# TowerLight.net
KiCad netlist of a schematic drawn in EAGLE
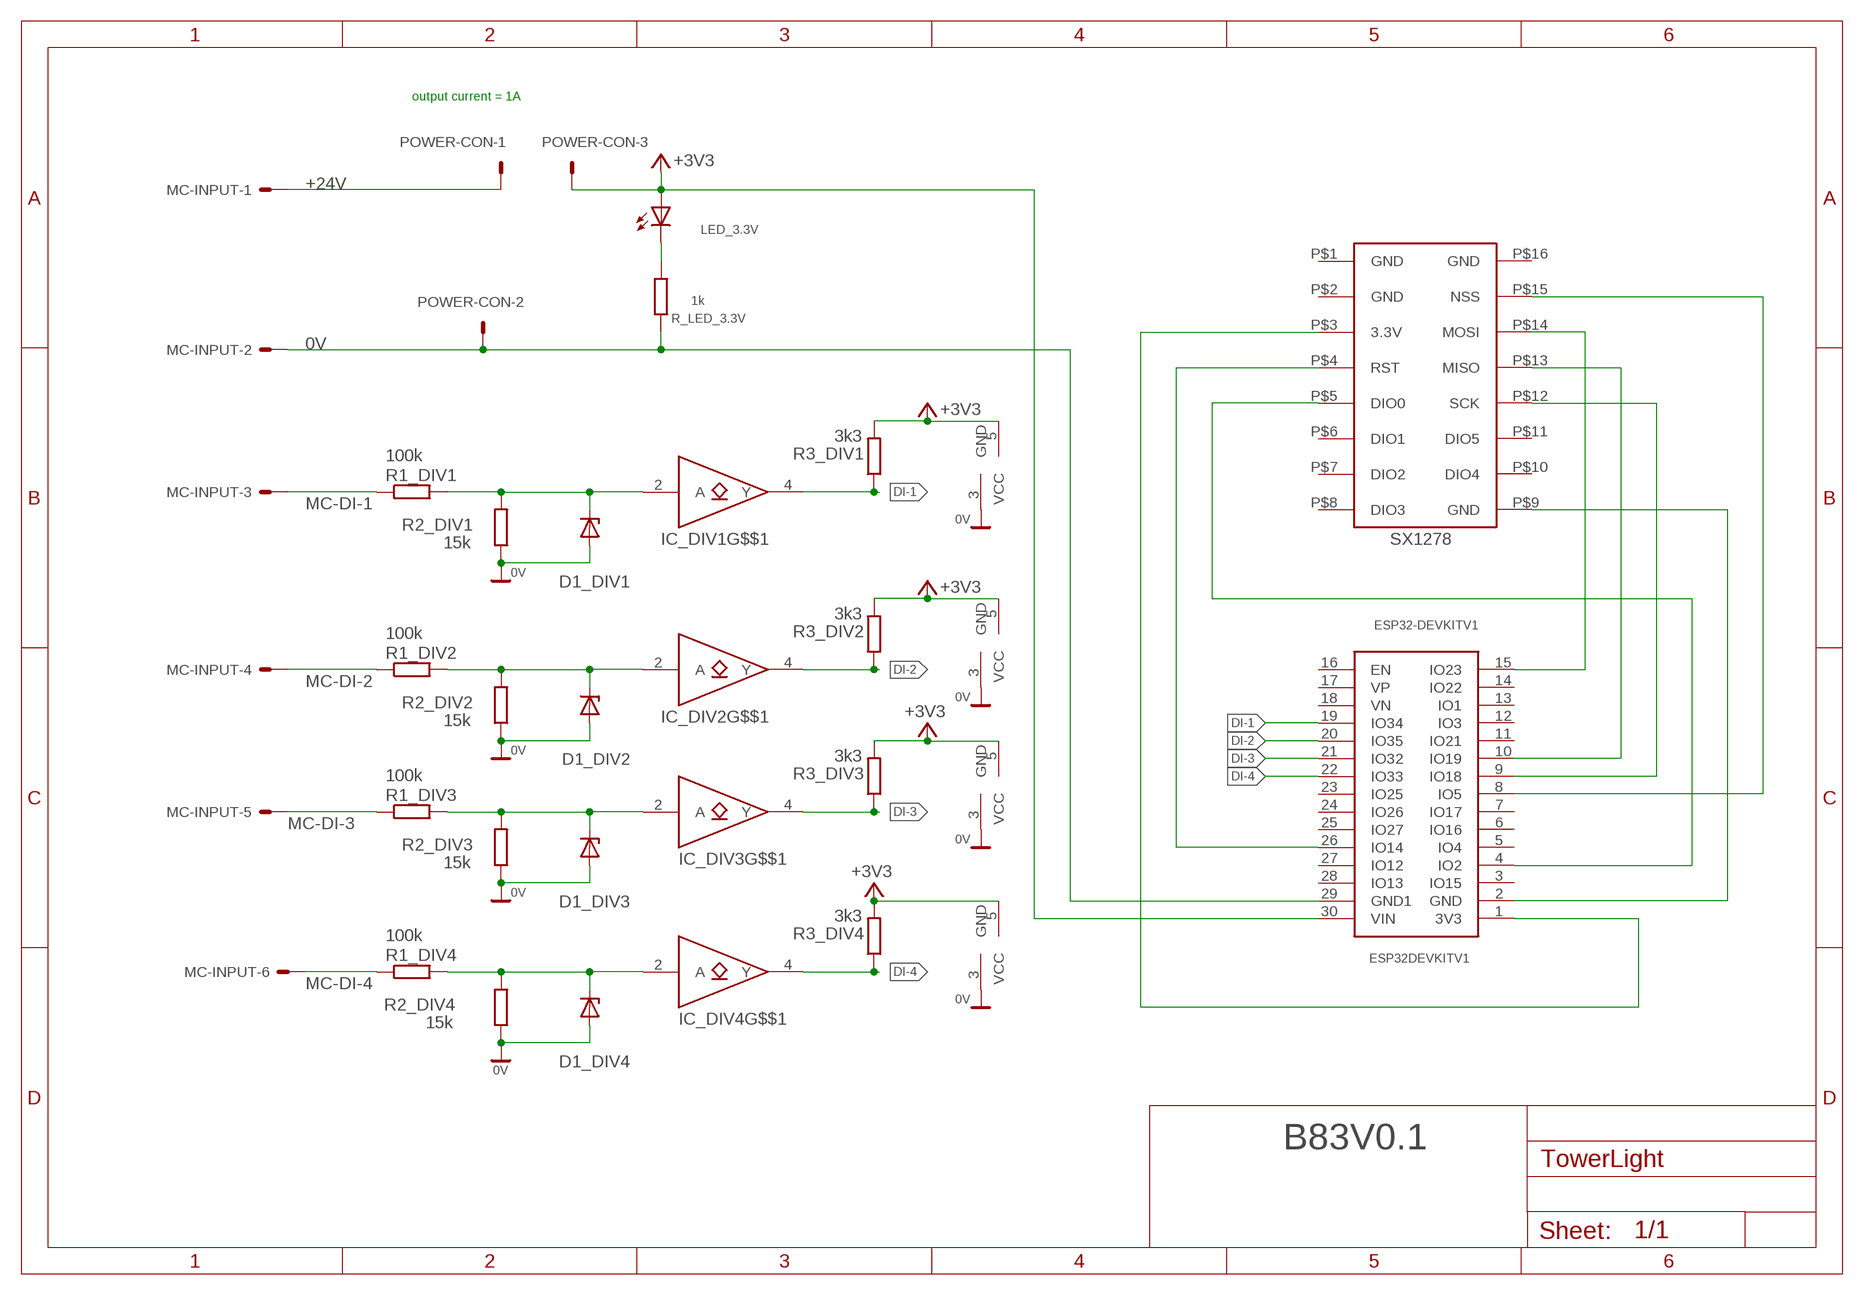
[diagram p0: schematic, sheet 1]

(export (version "E")
  (design (tool "Eeschema 10.0.6"))
  (components
    (comp (ref "D1_DIV1")
      (value "ZENER-DIODEDO34-7")
      (footprint "eagle-import:DO34Z7")
      (libsource (lib "eagle-import") (part "ZENER-DIODEDO34-7"))
    )
    (comp (ref "D1_DIV2")
      (value "ZENER-DIODEDO34-7")
      (footprint "eagle-import:DO34Z7")
      (libsource (lib "eagle-import") (part "ZENER-DIODEDO34-7"))
    )
    (comp (ref "D1_DIV3")
      (value "ZENER-DIODEDO34-7")
      (footprint "eagle-import:DO34Z7")
      (libsource (lib "eagle-import") (part "ZENER-DIODEDO34-7"))
    )
    (comp (ref "D1_DIV4")
      (value "ZENER-DIODEDO34-7")
      (footprint "eagle-import:DO34Z7")
      (libsource (lib "eagle-import") (part "ZENER-DIODEDO34-7"))
    )
    (comp (ref "ESP32DEVKITV1")
      (value "ESP32DEVKITV1")
      (footprint "eagle-import:ESP32-DEVKITV1")
      (libsource (lib "eagle-import") (part "ESP32DEVKITV1"))
    )
    (comp (ref "IC_DIV1")
      (value "SN74LVC1G07DBVR")
      (footprint "eagle-import:SOT23-5L")
      (libsource (lib "eagle-import") (part "SN74LVC1G07DBVR"))
    )
    (comp (ref "IC_DIV2")
      (value "SN74LVC1G07DBVR")
      (footprint "eagle-import:SOT23-5L")
      (libsource (lib "eagle-import") (part "SN74LVC1G07DBVR"))
    )
    (comp (ref "IC_DIV3")
      (value "SN74LVC1G07DBVR")
      (footprint "eagle-import:SOT23-5L")
      (libsource (lib "eagle-import") (part "SN74LVC1G07DBVR"))
    )
    (comp (ref "IC_DIV4")
      (value "SN74LVC1G07DBVR")
      (footprint "eagle-import:SOT23-5L")
      (libsource (lib "eagle-import") (part "SN74LVC1G07DBVR"))
    )
    (comp (ref "LED_3.3V")
      (value "LED_SUB")
      (footprint "eagle-import:LED_SUBMINI")
      (libsource (lib "eagle-import") (part "LED_SUB"))
    )
    (comp (ref "MC-INPUT")
      (value "22-05-7068-06")
      (footprint "eagle-import:7395-06")
      (libsource (lib "eagle-import") (part "22-?-0605-7068"))
    )
    (comp (ref "POWER-CON")
      (value "22-05-7038-03")
      (footprint "eagle-import:7395-03")
      (libsource (lib "eagle-import") (part "22-?-0305-7038"))
    )
    (comp (ref "R1_DIV1")
      (value "100k")
      (footprint "eagle-import:R1206")
      (libsource (lib "eagle-import") (part "R-EU_R1206"))
    )
    (comp (ref "R1_DIV2")
      (value "100k")
      (footprint "eagle-import:R1206")
      (libsource (lib "eagle-import") (part "R-EU_R1206"))
    )
    (comp (ref "R1_DIV3")
      (value "100k")
      (footprint "eagle-import:R1206")
      (libsource (lib "eagle-import") (part "R-EU_R1206"))
    )
    (comp (ref "R1_DIV4")
      (value "100k")
      (footprint "eagle-import:R1206")
      (libsource (lib "eagle-import") (part "R-EU_R1206"))
    )
    (comp (ref "R2_DIV1")
      (value "15k")
      (footprint "eagle-import:R1206")
      (libsource (lib "eagle-import") (part "R-EU_R1206"))
    )
    (comp (ref "R2_DIV2")
      (value "15k")
      (footprint "eagle-import:R1206")
      (libsource (lib "eagle-import") (part "R-EU_R1206"))
    )
    (comp (ref "R2_DIV3")
      (value "15k")
      (footprint "eagle-import:R1206")
      (libsource (lib "eagle-import") (part "R-EU_R1206"))
    )
    (comp (ref "R2_DIV4")
      (value "15k")
      (footprint "eagle-import:R1206")
      (libsource (lib "eagle-import") (part "R-EU_R1206"))
    )
    (comp (ref "R3_DIV1")
      (value "3k3")
      (footprint "eagle-import:R1206")
      (libsource (lib "eagle-import") (part "R-EU_R1206"))
    )
    (comp (ref "R3_DIV2")
      (value "3k3")
      (footprint "eagle-import:R1206")
      (libsource (lib "eagle-import") (part "R-EU_R1206"))
    )
    (comp (ref "R3_DIV3")
      (value "3k3")
      (footprint "eagle-import:R1206")
      (libsource (lib "eagle-import") (part "R-EU_R1206"))
    )
    (comp (ref "R3_DIV4")
      (value "3k3")
      (footprint "eagle-import:R1206")
      (libsource (lib "eagle-import") (part "R-EU_R1206"))
    )
    (comp (ref "R_LED_3.3V")
      (value "1k")
      (footprint "eagle-import:R1206")
      (libsource (lib "eagle-import") (part "R-EU_R1206"))
    )
    (comp (ref "U$2")
      (value "SX1278_MODULE")
      (footprint "eagle-import:SX1278_MODULE")
      (libsource (lib "eagle-import") (part "SX1278_MODULE"))
    )
  )
  (nets
    (net (code "1") (name "+3V3") (class "Default")
      (node (ref "ESP32DEVKITV1") (pin "30") (pinfunction "VIN_30") (pintype "bidirectional"))
      (node (ref "IC_DIV1") (pin "5") (pinfunction "VCC_5") (pintype "power_in"))
      (node (ref "IC_DIV2") (pin "5") (pinfunction "VCC_5") (pintype "power_in"))
      (node (ref "IC_DIV3") (pin "5") (pinfunction "VCC_5") (pintype "power_in"))
      (node (ref "IC_DIV4") (pin "5") (pinfunction "VCC_5") (pintype "power_in"))
      (node (ref "LED_3.3V") (pin "P$1") (pinfunction "A_P$1") (pintype "passive"))
      (node (ref "POWER-CON") (pin "3") (pinfunction "S_3") (pintype "passive"))
      (node (ref "R3_DIV1") (pin "2") (pinfunction "2_2") (pintype "passive"))
      (node (ref "R3_DIV2") (pin "2") (pinfunction "2_2") (pintype "passive"))
      (node (ref "R3_DIV3") (pin "2") (pinfunction "2_2") (pintype "passive"))
      (node (ref "R3_DIV4") (pin "2") (pinfunction "2_2") (pintype "passive"))
    )
    (net (code "2") (name "/+24V") (class "Default")
      (node (ref "MC-INPUT") (pin "1") (pinfunction "S_1") (pintype "passive"))
      (node (ref "POWER-CON") (pin "1") (pinfunction "S_1") (pintype "passive"))
    )
    (net (code "3") (name "/MC-DI-1") (class "Default")
      (node (ref "MC-INPUT") (pin "3") (pinfunction "S_3") (pintype "passive"))
      (node (ref "R1_DIV1") (pin "1") (pinfunction "1_1") (pintype "passive"))
    )
    (net (code "4") (name "/MC-DI-2") (class "Default")
      (node (ref "MC-INPUT") (pin "4") (pinfunction "S_4") (pintype "passive"))
      (node (ref "R1_DIV2") (pin "1") (pinfunction "1_1") (pintype "passive"))
    )
    (net (code "5") (name "/MC-DI-3") (class "Default")
      (node (ref "MC-INPUT") (pin "5") (pinfunction "S_5") (pintype "passive"))
      (node (ref "R1_DIV3") (pin "1") (pinfunction "1_1") (pintype "passive"))
    )
    (net (code "6") (name "/MC-DI-4") (class "Default")
      (node (ref "MC-INPUT") (pin "6") (pinfunction "S_6") (pintype "passive"))
      (node (ref "R1_DIV4") (pin "1") (pinfunction "1_1") (pintype "passive"))
    )
    (net (code "7") (name "0V") (class "Default")
      (node (ref "D1_DIV1") (pin "A") (pinfunction "A_A") (pintype "passive"))
      (node (ref "D1_DIV2") (pin "A") (pinfunction "A_A") (pintype "passive"))
      (node (ref "D1_DIV3") (pin "A") (pinfunction "A_A") (pintype "passive"))
      (node (ref "D1_DIV4") (pin "A") (pinfunction "A_A") (pintype "passive"))
      (node (ref "ESP32DEVKITV1") (pin "29") (pinfunction "GND1_29") (pintype "bidirectional"))
      (node (ref "IC_DIV1") (pin "3") (pinfunction "GND_3") (pintype "power_in"))
      (node (ref "IC_DIV2") (pin "3") (pinfunction "GND_3") (pintype "power_in"))
      (node (ref "IC_DIV3") (pin "3") (pinfunction "GND_3") (pintype "power_in"))
      (node (ref "IC_DIV4") (pin "3") (pinfunction "GND_3") (pintype "power_in"))
      (node (ref "MC-INPUT") (pin "2") (pinfunction "S_2") (pintype "passive"))
      (node (ref "POWER-CON") (pin "2") (pinfunction "S_2") (pintype "passive"))
      (node (ref "R2_DIV1") (pin "1") (pinfunction "1_1") (pintype "passive"))
      (node (ref "R2_DIV2") (pin "1") (pinfunction "1_1") (pintype "passive"))
      (node (ref "R2_DIV3") (pin "1") (pinfunction "1_1") (pintype "passive"))
      (node (ref "R2_DIV4") (pin "1") (pinfunction "1_1") (pintype "passive"))
      (node (ref "R_LED_3.3V") (pin "2") (pinfunction "2_2") (pintype "passive"))
    )
    (net (code "8") (name "DI-1") (class "Default")
      (node (ref "ESP32DEVKITV1") (pin "19") (pinfunction "IO34_19") (pintype "bidirectional"))
      (node (ref "IC_DIV1") (pin "4") (pinfunction "Y_4") (pintype "bidirectional"))
      (node (ref "R3_DIV1") (pin "1") (pinfunction "1_1") (pintype "passive"))
    )
    (net (code "9") (name "DI-2") (class "Default")
      (node (ref "ESP32DEVKITV1") (pin "20") (pinfunction "IO35_20") (pintype "bidirectional"))
      (node (ref "IC_DIV2") (pin "4") (pinfunction "Y_4") (pintype "bidirectional"))
      (node (ref "R3_DIV2") (pin "1") (pinfunction "1_1") (pintype "passive"))
    )
    (net (code "10") (name "DI-3") (class "Default")
      (node (ref "ESP32DEVKITV1") (pin "21") (pinfunction "IO32_21") (pintype "bidirectional"))
      (node (ref "IC_DIV3") (pin "4") (pinfunction "Y_4") (pintype "bidirectional"))
      (node (ref "R3_DIV3") (pin "1") (pinfunction "1_1") (pintype "passive"))
    )
    (net (code "11") (name "DI-4") (class "Default")
      (node (ref "ESP32DEVKITV1") (pin "22") (pinfunction "IO33_22") (pintype "bidirectional"))
      (node (ref "IC_DIV4") (pin "4") (pinfunction "Y_4") (pintype "bidirectional"))
      (node (ref "R3_DIV4") (pin "1") (pinfunction "1_1") (pintype "passive"))
    )
    (net (code "12") (name "Net-(ESP32DEVKITV1-3V3)") (class "Default")
      (node (ref "ESP32DEVKITV1") (pin "1") (pinfunction "3V3_1") (pintype "bidirectional"))
      (node (ref "U$2") (pin "P$3") (pinfunction "3.3V_P$3") (pintype "bidirectional"))
    )
    (net (code "13") (name "Net-(ESP32DEVKITV1-GND)") (class "Default")
      (node (ref "ESP32DEVKITV1") (pin "2") (pinfunction "GND_2") (pintype "bidirectional"))
      (node (ref "U$2") (pin "P$9") (pinfunction "GND_P$9") (pintype "bidirectional"))
    )
    (net (code "14") (name "Net-(ESP32DEVKITV1-IO2)") (class "Default")
      (node (ref "ESP32DEVKITV1") (pin "4") (pinfunction "IO2_4") (pintype "bidirectional"))
      (node (ref "U$2") (pin "P$5") (pinfunction "DIO0_P$5") (pintype "bidirectional"))
    )
    (net (code "15") (name "Net-(ESP32DEVKITV1-IO5)") (class "Default")
      (node (ref "ESP32DEVKITV1") (pin "8") (pinfunction "IO5_8") (pintype "bidirectional"))
      (node (ref "U$2") (pin "P$15") (pinfunction "NSS_P$15") (pintype "bidirectional"))
    )
    (net (code "16") (name "Net-(ESP32DEVKITV1-IO14)") (class "Default")
      (node (ref "ESP32DEVKITV1") (pin "26") (pinfunction "IO14_26") (pintype "bidirectional"))
      (node (ref "U$2") (pin "P$4") (pinfunction "RST_P$4") (pintype "bidirectional"))
    )
    (net (code "17") (name "Net-(ESP32DEVKITV1-IO18)") (class "Default")
      (node (ref "ESP32DEVKITV1") (pin "9") (pinfunction "IO18_9") (pintype "bidirectional"))
      (node (ref "U$2") (pin "P$12") (pinfunction "SCK_P$12") (pintype "bidirectional"))
    )
    (net (code "18") (name "Net-(ESP32DEVKITV1-IO19)") (class "Default")
      (node (ref "ESP32DEVKITV1") (pin "10") (pinfunction "IO19_10") (pintype "bidirectional"))
      (node (ref "U$2") (pin "P$13") (pinfunction "MISO_P$13") (pintype "bidirectional"))
    )
    (net (code "19") (name "Net-(ESP32DEVKITV1-IO23)") (class "Default")
      (node (ref "ESP32DEVKITV1") (pin "15") (pinfunction "IO23_15") (pintype "bidirectional"))
      (node (ref "U$2") (pin "P$14") (pinfunction "MOSI_P$14") (pintype "bidirectional"))
    )
    (net (code "20") (name "Net-(IC_DIV1B-A)") (class "Default")
      (node (ref "D1_DIV1") (pin "C") (pinfunction "C_C") (pintype "passive"))
      (node (ref "IC_DIV1") (pin "2") (pinfunction "A_2") (pintype "bidirectional"))
      (node (ref "R1_DIV1") (pin "2") (pinfunction "2_2") (pintype "passive"))
      (node (ref "R2_DIV1") (pin "2") (pinfunction "2_2") (pintype "passive"))
    )
    (net (code "21") (name "Net-(IC_DIV2B-A)") (class "Default")
      (node (ref "D1_DIV2") (pin "C") (pinfunction "C_C") (pintype "passive"))
      (node (ref "IC_DIV2") (pin "2") (pinfunction "A_2") (pintype "bidirectional"))
      (node (ref "R1_DIV2") (pin "2") (pinfunction "2_2") (pintype "passive"))
      (node (ref "R2_DIV2") (pin "2") (pinfunction "2_2") (pintype "passive"))
    )
    (net (code "22") (name "Net-(IC_DIV3B-A)") (class "Default")
      (node (ref "D1_DIV3") (pin "C") (pinfunction "C_C") (pintype "passive"))
      (node (ref "IC_DIV3") (pin "2") (pinfunction "A_2") (pintype "bidirectional"))
      (node (ref "R1_DIV3") (pin "2") (pinfunction "2_2") (pintype "passive"))
      (node (ref "R2_DIV3") (pin "2") (pinfunction "2_2") (pintype "passive"))
    )
    (net (code "23") (name "Net-(IC_DIV4B-A)") (class "Default")
      (node (ref "D1_DIV4") (pin "C") (pinfunction "C_C") (pintype "passive"))
      (node (ref "IC_DIV4") (pin "2") (pinfunction "A_2") (pintype "bidirectional"))
      (node (ref "R1_DIV4") (pin "2") (pinfunction "2_2") (pintype "passive"))
      (node (ref "R2_DIV4") (pin "2") (pinfunction "2_2") (pintype "passive"))
    )
    (net (code "24") (name "Net-(LED_3.3V-C)") (class "Default")
      (node (ref "LED_3.3V") (pin "P$2") (pinfunction "C_P$2") (pintype "passive"))
      (node (ref "R_LED_3.3V") (pin "1") (pinfunction "1_1") (pintype "passive"))
    )
    (net (code "25") (name "unconnected-(ESP32DEVKITV1-EN-Pad16)") (class "Default")
      (node (ref "ESP32DEVKITV1") (pin "16") (pinfunction "EN_16") (pintype "bidirectional"))
    )
    (net (code "26") (name "unconnected-(ESP32DEVKITV1-IO1-Pad13)") (class "Default")
      (node (ref "ESP32DEVKITV1") (pin "13") (pinfunction "IO1_13") (pintype "bidirectional"))
    )
    (net (code "27") (name "unconnected-(ESP32DEVKITV1-IO3-Pad12)") (class "Default")
      (node (ref "ESP32DEVKITV1") (pin "12") (pinfunction "IO3_12") (pintype "bidirectional"))
    )
    (net (code "28") (name "unconnected-(ESP32DEVKITV1-IO4-Pad5)") (class "Default")
      (node (ref "ESP32DEVKITV1") (pin "5") (pinfunction "IO4_5") (pintype "bidirectional"))
    )
    (net (code "29") (name "unconnected-(ESP32DEVKITV1-IO12-Pad27)") (class "Default")
      (node (ref "ESP32DEVKITV1") (pin "27") (pinfunction "IO12_27") (pintype "bidirectional"))
    )
    (net (code "30") (name "unconnected-(ESP32DEVKITV1-IO13-Pad28)") (class "Default")
      (node (ref "ESP32DEVKITV1") (pin "28") (pinfunction "IO13_28") (pintype "bidirectional"))
    )
    (net (code "31") (name "unconnected-(ESP32DEVKITV1-IO15-Pad3)") (class "Default")
      (node (ref "ESP32DEVKITV1") (pin "3") (pinfunction "IO15_3") (pintype "bidirectional"))
    )
    (net (code "32") (name "unconnected-(ESP32DEVKITV1-IO16-Pad6)") (class "Default")
      (node (ref "ESP32DEVKITV1") (pin "6") (pinfunction "IO16_6") (pintype "bidirectional"))
    )
    (net (code "33") (name "unconnected-(ESP32DEVKITV1-IO17-Pad7)") (class "Default")
      (node (ref "ESP32DEVKITV1") (pin "7") (pinfunction "IO17_7") (pintype "bidirectional"))
    )
    (net (code "34") (name "unconnected-(ESP32DEVKITV1-IO21-Pad11)") (class "Default")
      (node (ref "ESP32DEVKITV1") (pin "11") (pinfunction "IO21_11") (pintype "bidirectional"))
    )
    (net (code "35") (name "unconnected-(ESP32DEVKITV1-IO22-Pad14)") (class "Default")
      (node (ref "ESP32DEVKITV1") (pin "14") (pinfunction "IO22_14") (pintype "bidirectional"))
    )
    (net (code "36") (name "unconnected-(ESP32DEVKITV1-IO25-Pad23)") (class "Default")
      (node (ref "ESP32DEVKITV1") (pin "23") (pinfunction "IO25_23") (pintype "bidirectional"))
    )
    (net (code "37") (name "unconnected-(ESP32DEVKITV1-IO26-Pad24)") (class "Default")
      (node (ref "ESP32DEVKITV1") (pin "24") (pinfunction "IO26_24") (pintype "bidirectional"))
    )
    (net (code "38") (name "unconnected-(ESP32DEVKITV1-IO27-Pad25)") (class "Default")
      (node (ref "ESP32DEVKITV1") (pin "25") (pinfunction "IO27_25") (pintype "bidirectional"))
    )
    (net (code "39") (name "unconnected-(ESP32DEVKITV1-VN-Pad18)") (class "Default")
      (node (ref "ESP32DEVKITV1") (pin "18") (pinfunction "VN_18") (pintype "bidirectional"))
    )
    (net (code "40") (name "unconnected-(ESP32DEVKITV1-VP-Pad17)") (class "Default")
      (node (ref "ESP32DEVKITV1") (pin "17") (pinfunction "VP_17") (pintype "bidirectional"))
    )
    (net (code "41") (name "unconnected-(U$2-DIO1-PadP$6)") (class "Default")
      (node (ref "U$2") (pin "P$6") (pinfunction "DIO1_P$6") (pintype "bidirectional"))
    )
    (net (code "42") (name "unconnected-(U$2-DIO2-PadP$7)") (class "Default")
      (node (ref "U$2") (pin "P$7") (pinfunction "DIO2_P$7") (pintype "bidirectional"))
    )
    (net (code "43") (name "unconnected-(U$2-DIO3-PadP$8)") (class "Default")
      (node (ref "U$2") (pin "P$8") (pinfunction "DIO3_P$8") (pintype "bidirectional"))
    )
    (net (code "44") (name "unconnected-(U$2-DIO4-PadP$10)") (class "Default")
      (node (ref "U$2") (pin "P$10") (pinfunction "DIO4_P$10") (pintype "bidirectional"))
    )
    (net (code "45") (name "unconnected-(U$2-DIO5-PadP$11)") (class "Default")
      (node (ref "U$2") (pin "P$11") (pinfunction "DIO5_P$11") (pintype "bidirectional"))
    )
    (net (code "46") (name "unconnected-(U$2-GND-PadP$1)") (class "Default")
      (node (ref "U$2") (pin "P$1") (pinfunction "GND_P$1") (pintype "bidirectional"))
    )
    (net (code "47") (name "unconnected-(U$2-GND-PadP$2)") (class "Default")
      (node (ref "U$2") (pin "P$2") (pinfunction "GND_P$2") (pintype "bidirectional"))
    )
    (net (code "48") (name "unconnected-(U$2-GND-PadP$16)") (class "Default")
      (node (ref "U$2") (pin "P$16") (pinfunction "GND_P$16") (pintype "bidirectional"))
    )
  )
)
